# FXOS8700_without_Extender.net
KiCad netlist of a schematic drawn in EAGLE
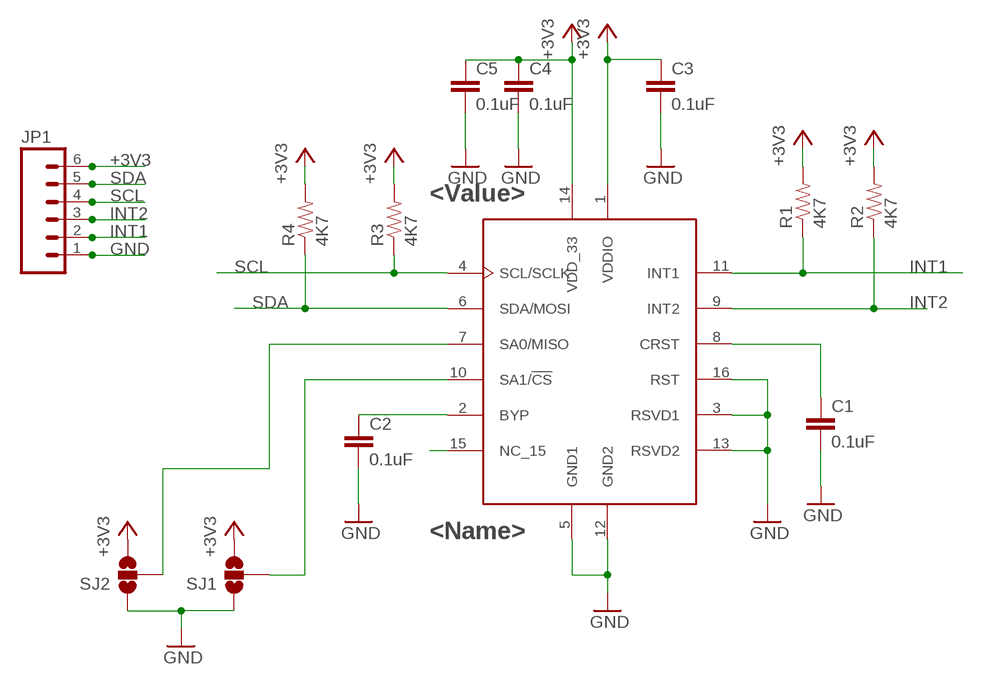
[diagram p0: schematic, sheet 1]

(export (version "E")
  (design (tool "Eeschema 10.0.6"))
  (components
    (comp (ref "C1")
      (value "0.1uF")
      (footprint "eagle-import:0805")
      (libsource (lib "eagle-import") (part "CAP0805"))
    )
    (comp (ref "C2")
      (value "0.1uF")
      (footprint "eagle-import:0805")
      (libsource (lib "eagle-import") (part "CAP0805"))
    )
    (comp (ref "C3")
      (value "0.1uF")
      (footprint "eagle-import:0805")
      (libsource (lib "eagle-import") (part "CAP0805"))
    )
    (comp (ref "C4")
      (value "0.1uF")
      (footprint "eagle-import:0805")
      (libsource (lib "eagle-import") (part "CAP0805"))
    )
    (comp (ref "C5")
      (value "0.1uF")
      (footprint "eagle-import:0805")
      (libsource (lib "eagle-import") (part "CAP0805"))
    )
    (comp (ref "JP1")
      (value "M06LOCK")
      (footprint "eagle-import:1X06_LOCK")
      (libsource (lib "eagle-import") (part "M06LOCK"))
    )
    (comp (ref "R1")
      (value "4K7")
      (footprint "eagle-import:0805")
      (libsource (lib "eagle-import") (part "RESISTOR0805-RES"))
    )
    (comp (ref "R2")
      (value "4K7")
      (footprint "eagle-import:0805")
      (libsource (lib "eagle-import") (part "RESISTOR0805-RES"))
    )
    (comp (ref "R3")
      (value "4K7")
      (footprint "eagle-import:0805")
      (libsource (lib "eagle-import") (part "RESISTOR0805-RES"))
    )
    (comp (ref "R4")
      (value "4K7")
      (footprint "eagle-import:0805")
      (libsource (lib "eagle-import") (part "RESISTOR0805-RES"))
    )
    (comp (ref "SJ1")
      (value "SOLDERJUMPER_2WAYPASTE1&2")
      (footprint "eagle-import:SJ_3_PASTE1&2")
      (libsource (lib "eagle-import") (part "SOLDERJUMPER_2WAYPASTE1&2"))
    )
    (comp (ref "SJ2")
      (value "SOLDERJUMPER_2WAYPASTE1&2")
      (footprint "eagle-import:SJ_3_PASTE1&2")
      (libsource (lib "eagle-import") (part "SOLDERJUMPER_2WAYPASTE1&2"))
    )
    (comp (ref "U$1")
      (value "FXOS870CQ")
      (footprint "eagle-import:QFN16_0P5_3X3")
      (libsource (lib "eagle-import") (part "FXOS870CQ"))
    )
  )
  (nets
    (net (code "1") (name "+3V3") (class "Default")
      (node (ref "C3") (pin "1") (pinfunction "1_1") (pintype "passive"))
      (node (ref "C4") (pin "1") (pinfunction "1_1") (pintype "passive"))
      (node (ref "C5") (pin "1") (pinfunction "1_1") (pintype "passive"))
      (node (ref "JP1") (pin "6") (pinfunction "6_6") (pintype "passive"))
      (node (ref "R1") (pin "2") (pinfunction "2_2") (pintype "passive"))
      (node (ref "R2") (pin "2") (pinfunction "2_2") (pintype "passive"))
      (node (ref "R3") (pin "2") (pinfunction "2_2") (pintype "passive"))
      (node (ref "R4") (pin "2") (pinfunction "2_2") (pintype "passive"))
      (node (ref "SJ1") (pin "3") (pinfunction "3_3") (pintype "passive"))
      (node (ref "SJ2") (pin "3") (pinfunction "3_3") (pintype "passive"))
      (node (ref "U$1") (pin "1") (pinfunction "VDDIO_1") (pintype "power_in"))
      (node (ref "U$1") (pin "14") (pinfunction "VDD_33_14") (pintype "power_in"))
    )
    (net (code "2") (name "/INT1") (class "Default")
      (node (ref "JP1") (pin "2") (pinfunction "2_2") (pintype "passive"))
      (node (ref "R1") (pin "1") (pinfunction "1_1") (pintype "passive"))
      (node (ref "U$1") (pin "11") (pinfunction "INT1_11") (pintype "output"))
    )
    (net (code "3") (name "/INT2") (class "Default")
      (node (ref "JP1") (pin "3") (pinfunction "3_3") (pintype "passive"))
      (node (ref "R2") (pin "1") (pinfunction "1_1") (pintype "passive"))
      (node (ref "U$1") (pin "9") (pinfunction "INT2_9") (pintype "output"))
    )
    (net (code "4") (name "/SCL") (class "Default")
      (node (ref "JP1") (pin "4") (pinfunction "4_4") (pintype "passive"))
      (node (ref "R3") (pin "1") (pinfunction "1_1") (pintype "passive"))
      (node (ref "U$1") (pin "4") (pinfunction "SCL/SCLK_4") (pintype "bidirectional"))
    )
    (net (code "5") (name "/SDA") (class "Default")
      (node (ref "JP1") (pin "5") (pinfunction "5_5") (pintype "passive"))
      (node (ref "R4") (pin "1") (pinfunction "1_1") (pintype "passive"))
      (node (ref "U$1") (pin "6") (pinfunction "SDA/MOSI_6") (pintype "bidirectional"))
    )
    (net (code "6") (name "GND") (class "Default")
      (node (ref "C1") (pin "2") (pinfunction "2_2") (pintype "passive"))
      (node (ref "C2") (pin "2") (pinfunction "2_2") (pintype "passive"))
      (node (ref "C3") (pin "2") (pinfunction "2_2") (pintype "passive"))
      (node (ref "C4") (pin "2") (pinfunction "2_2") (pintype "passive"))
      (node (ref "C5") (pin "2") (pinfunction "2_2") (pintype "passive"))
      (node (ref "JP1") (pin "1") (pinfunction "1_1") (pintype "passive"))
      (node (ref "SJ1") (pin "1") (pinfunction "1_1") (pintype "passive"))
      (node (ref "SJ2") (pin "1") (pinfunction "1_1") (pintype "passive"))
      (node (ref "U$1") (pin "12") (pinfunction "GND2_12") (pintype "power_in"))
      (node (ref "U$1") (pin "13") (pinfunction "RSVD2_13") (pintype "power_in"))
      (node (ref "U$1") (pin "16") (pinfunction "RST_16") (pintype "input"))
      (node (ref "U$1") (pin "3") (pinfunction "RSVD1_3") (pintype "power_in"))
      (node (ref "U$1") (pin "5") (pinfunction "GND1_5") (pintype "power_in"))
    )
    (net (code "7") (name "Net-(U$1-BYP)") (class "Default")
      (node (ref "C2") (pin "1") (pinfunction "1_1") (pintype "passive"))
      (node (ref "U$1") (pin "2") (pinfunction "BYP_2") (pintype "bidirectional"))
    )
    (net (code "8") (name "Net-(U$1-CRST)") (class "Default")
      (node (ref "C1") (pin "1") (pinfunction "1_1") (pintype "passive"))
      (node (ref "U$1") (pin "8") (pinfunction "CRST_8") (pintype "passive"))
    )
    (net (code "9") (name "Net-(U$1-SA0{slash}MISO)") (class "Default")
      (node (ref "SJ2") (pin "2") (pinfunction "2_2") (pintype "passive"))
      (node (ref "U$1") (pin "7") (pinfunction "SA0/MISO_7") (pintype "bidirectional"))
    )
    (net (code "10") (name "Net-(U$1-SA1{slash}~{CS})") (class "Default")
      (node (ref "SJ1") (pin "2") (pinfunction "2_2") (pintype "passive"))
      (node (ref "U$1") (pin "10") (pinfunction "SA1/~{CS}_10") (pintype "bidirectional"))
    )
    (net (code "11") (name "unconnected-(U$1-NC_15-Pad15)") (class "Default")
      (node (ref "U$1") (pin "15") (pinfunction "NC_15_15") (pintype "no_connect"))
    )
  )
)
